# Sheet1.net
KiCad netlist of a schematic drawn in Altium Designer
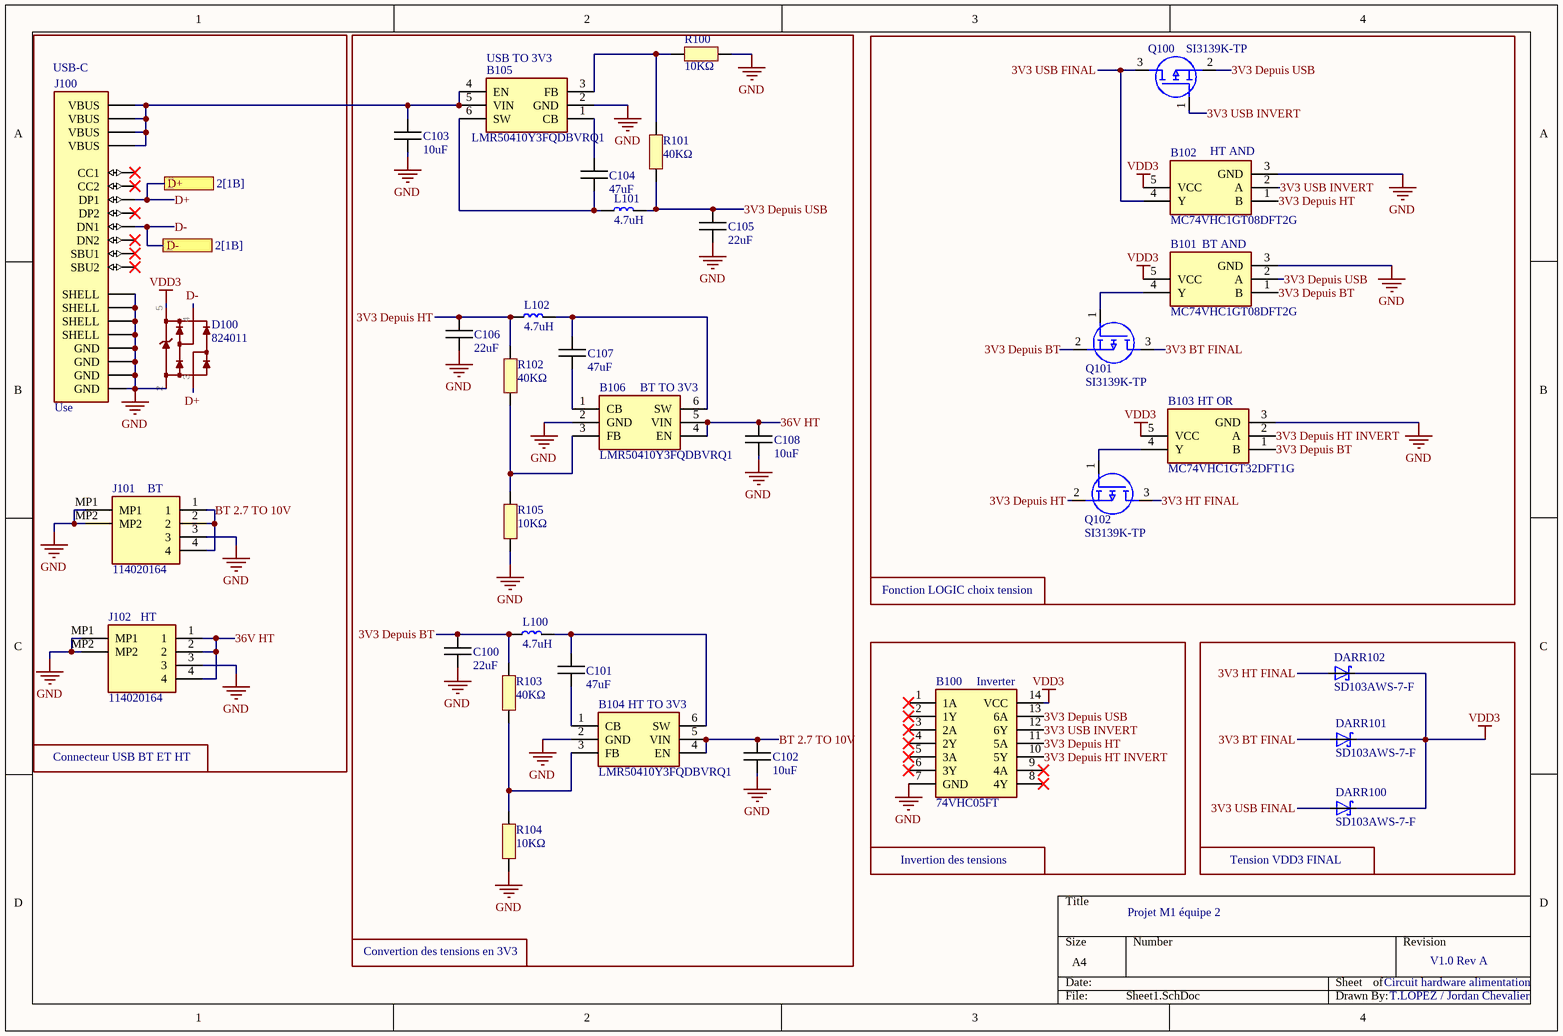
[diagram p0: Sheet1.SchDoc]

(export (version "E")
  (design (tool "Eeschema 10.0.6"))
  (components
    (comp (ref "B100")
      (value "74VHC05FT")
      (footprint "SOP65P640X120-14N")
      (description "Logic Gates CMOS LOGIC IC INVERTER")
      (fields (field (name "MOUSER PART NUMBER") "757-74VHC05FT"))
      (libsource (lib "SCHLibrary") (part "74VHC05FT"))
    )
    (comp (ref "B101")
      (value "MC74VHC1GT08DFT2G")
      (footprint "SOT65P210X110-5N")
      (description "Single 2-Input AND Gate, TTL Level")
      (libsource (lib "SCHLibrary") (part "MC74VHC1GT08DFT2G"))
    )
    (comp (ref "B102")
      (value "MC74VHC1GT08DFT2G")
      (footprint "SOT65P210X110-5N")
      (description "Single 2-Input AND Gate, TTL Level")
      (libsource (lib "SCHLibrary") (part "MC74VHC1GT08DFT2G"))
    )
    (comp (ref "B103")
      (value "MC74VHC1GT32DFT1G")
      (footprint "SOT65P210X110-5N")
      (description "Single 2-Input OR Gate, TTL Level")
      (fields (field (name "MOUSER PART NUMBER") "863-C74VHC1GT32DFT1G"))
      (libsource (lib "SCHLibrary") (part "MC74VHC1GT32DFT1G"))
    )
    (comp (ref "B104")
      (value "LMR50410Y3FQDBVRQ1")
      (footprint "SOT95P280X145-6N")
      (fields (field (name "MOUSER PART NUMBER") "595-R50410Y3FQDBVRQ1"))
      (libsource (lib "SCHLibrary") (part "LMR50410Y3FQDBVRQ1"))
    )
    (comp (ref "B105")
      (value "LMR50410Y3FQDBVRQ1")
      (footprint "SOT95P280X145-6N")
      (fields (field (name "MOUSER PART NUMBER") "595-R50410Y3FQDBVRQ1"))
      (libsource (lib "") (part "LMR50410Y3FQDBVRQ1_1"))
    )
    (comp (ref "B106")
      (value "LMR50410Y3FQDBVRQ1")
      (footprint "SOT95P280X145-6N")
      (fields (field (name "MOUSER PART NUMBER") "595-R50410Y3FQDBVRQ1"))
      (libsource (lib "SCHLibrary") (part "LMR50410Y3FQDBVRQ1"))
    )
    (comp (ref "C100")
      (value "22uF")
      (footprint "CAPC1005X06N")
      (libsource (lib "SCHLibrary") (part "Capacitor"))
    )
    (comp (ref "C101")
      (value "47uF")
      (footprint "CAPC1005X06N")
      (libsource (lib "SCHLibrary") (part "Capacitor"))
    )
    (comp (ref "C102")
      (value "10uF")
      (footprint "CAPC1005X06N")
      (libsource (lib "SCHLibrary") (part "Capacitor"))
    )
    (comp (ref "C103")
      (value "10uF")
      (footprint "CAPC1005X06N")
      (libsource (lib "SCHLibrary") (part "Capacitor"))
    )
    (comp (ref "C104")
      (value "47uF")
      (footprint "CAPC1005X06N")
      (libsource (lib "SCHLibrary") (part "Capacitor"))
    )
    (comp (ref "C105")
      (value "22uF")
      (footprint "CAPC1005X06N")
      (libsource (lib "SCHLibrary") (part "Capacitor"))
    )
    (comp (ref "C106")
      (value "22uF")
      (footprint "CAPC1005X06N")
      (libsource (lib "SCHLibrary") (part "Capacitor"))
    )
    (comp (ref "C107")
      (value "47uF")
      (footprint "CAPC1005X06N")
      (libsource (lib "SCHLibrary") (part "Capacitor"))
    )
    (comp (ref "C108")
      (value "10uF")
      (footprint "CAPC1005X06N")
      (libsource (lib "SCHLibrary") (part "Capacitor"))
    )
    (comp (ref "D100") (value "824011") (footprint "824011") (libsource (lib "SCHLibrary") (part "824011")))
    (comp (ref "DARR100")
      (value "SD103AWS-7-F")
      (footprint "SD103AWS-7-F")
      (description "Diode Array 3 Independent Schottky 40V 175mA Surface Mount 6-TSSOP, SC-88, SOT-363")
      (libsource (lib "SCHLibrary") (part "SD103AWS-7-F"))
    )
    (comp (ref "DARR101")
      (value "SD103AWS-7-F")
      (footprint "SD103AWS-7-F")
      (description "Diode Array 3 Independent Schottky 40V 175mA Surface Mount 6-TSSOP, SC-88, SOT-363")
      (libsource (lib "SCHLibrary") (part "SD103AWS-7-F"))
    )
    (comp (ref "DARR102")
      (value "SD103AWS-7-F")
      (footprint "SD103AWS-7-F")
      (description "Diode Array 3 Independent Schottky 40V 175mA Surface Mount 6-TSSOP, SC-88, SOT-363")
      (libsource (lib "SCHLibrary") (part "SD103AWS-7-F"))
    )
    (comp (ref "J100")
      (value "Use")
      (footprint "USB4085-GF-A")
      (description "Connecteurs USB USB Type C, 2.0, Rec, TH , G/F, RA , Top Mnt, T & R")
      (libsource (lib "SCHLibrary") (part "USB4085-GF-A"))
    )
    (comp (ref "J101")
      (value "114020164")
      (footprint "114020164")
      (description "Seeed Studio Accessories Grove Female Header - SMD-4P-2.0mm-90D-20Pcs")
      (fields (field (name "MOUSER PART NUMBER") "713-114020164"))
      (libsource (lib "SCHLibrary") (part "114020164"))
    )
    (comp (ref "J102")
      (value "114020164")
      (footprint "114020164")
      (description "Seeed Studio Accessories Grove Female Header - SMD-4P-2.0mm-90D-20Pcs")
      (fields (field (name "MOUSER PART NUMBER") "713-114020164"))
      (libsource (lib "SCHLibrary") (part "114020164"))
    )
    (comp (ref "L100")
      (value "4.7uH")
      (footprint "LQPC1005X06N")
      (libsource (lib "SCHLibrary") (part "Bobine"))
    )
    (comp (ref "L101")
      (value "4.7uH")
      (footprint "LQPC1005X06N")
      (libsource (lib "SCHLibrary") (part "Bobine"))
    )
    (comp (ref "L102")
      (value "4.7uH")
      (footprint "LQPC1005X06N")
      (libsource (lib "SCHLibrary") (part "Bobine"))
    )
    (comp (ref "Q100")
      (value "SI3139K-TP")
      (footprint "SI3139K-TP")
      (description "MOSFET P-Channel MOSFET")
      (libsource (lib "SCHLibrary") (part "SI3139K-TP"))
    )
    (comp (ref "Q101")
      (value "SI3139K-TP")
      (footprint "SI3139K-TP")
      (description "MOSFET P-Channel MOSFET")
      (libsource (lib "SCHLibrary") (part "SI3139K-TP"))
    )
    (comp (ref "Q102")
      (value "SI3139K-TP")
      (footprint "SI3139K-TP")
      (description "MOSFET P-Channel MOSFET")
      (libsource (lib "SCHLibrary") (part "SI3139K-TP"))
    )
    (comp (ref "R100") (value "10KΩ") (footprint "RESC1005X06N") (libsource (lib "") (part "Resistor_2")))
    (comp (ref "R101") (value "40KΩ") (footprint "RESC1005X06N") (libsource (lib "") (part "Resistor_1")))
    (comp (ref "R102")
      (value "40KΩ")
      (footprint "RESC1005X06N")
      (libsource (lib "SCHLibrary") (part "Resistor"))
    )
    (comp (ref "R103")
      (value "40KΩ")
      (footprint "RESC1005X06N")
      (libsource (lib "SCHLibrary") (part "Resistor"))
    )
    (comp (ref "R104")
      (value "10KΩ")
      (footprint "RESC1005X06N")
      (libsource (lib "SCHLibrary") (part "Resistor"))
    )
    (comp (ref "R105")
      (value "10KΩ")
      (footprint "RESC1005X06N")
      (libsource (lib "SCHLibrary") (part "Resistor"))
    )
  )
  (nets
    (net (code "1") (name "/3V3 BT FINAL") (class "Default")
      (node (ref "DARR101") (pin "2") (pinfunction "A_2") (pintype "passive"))
      (node (ref "Q101") (pin "3") (pinfunction "D_3") (pintype "passive"))
    )
    (net (code "2") (name "/3V3 Depuis BT") (class "Default")
      (node (ref "B101") (pin "1") (pinfunction "B_1") (pintype "passive"))
      (node (ref "B103") (pin "1") (pinfunction "B_1") (pintype "passive"))
      (node (ref "C100") (pin "1") (pinfunction "1_1") (pintype "passive"))
      (node (ref "L100") (pin "1") (pinfunction "1_1") (pintype "passive"))
      (node (ref "Q101") (pin "2") (pinfunction "S_2") (pintype "passive"))
      (node (ref "R103") (pin "2") (pinfunction "2_2") (pintype "passive"))
    )
    (net (code "3") (name "/3V3 Depuis HT") (class "Default")
      (node (ref "B100") (pin "11") (pinfunction "5A_11") (pintype "passive"))
      (node (ref "B102") (pin "1") (pinfunction "B_1") (pintype "passive"))
      (node (ref "C106") (pin "1") (pinfunction "1_1") (pintype "passive"))
      (node (ref "L102") (pin "1") (pinfunction "1_1") (pintype "passive"))
      (node (ref "Q102") (pin "2") (pinfunction "S_2") (pintype "passive"))
      (node (ref "R102") (pin "2") (pinfunction "2_2") (pintype "passive"))
    )
    (net (code "4") (name "/3V3 Depuis HT INVERT") (class "Default")
      (node (ref "B100") (pin "10") (pinfunction "5Y_10") (pintype "passive"))
      (node (ref "B103") (pin "2") (pinfunction "A_2") (pintype "passive"))
    )
    (net (code "5") (name "/3V3 Depuis USB") (class "Default")
      (node (ref "B100") (pin "13") (pinfunction "6A_13") (pintype "passive"))
      (node (ref "B101") (pin "2") (pinfunction "A_2") (pintype "passive"))
      (node (ref "C105") (pin "1") (pinfunction "1_1") (pintype "passive"))
      (node (ref "L101") (pin "2") (pinfunction "2_2") (pintype "passive"))
      (node (ref "Q100") (pin "2") (pinfunction "S_2") (pintype "passive"))
      (node (ref "R101") (pin "2") (pinfunction "2_2") (pintype "passive"))
    )
    (net (code "6") (name "/3V3 HT FINAL") (class "Default")
      (node (ref "DARR102") (pin "2") (pinfunction "A_2") (pintype "passive"))
      (node (ref "Q102") (pin "3") (pinfunction "D_3") (pintype "passive"))
    )
    (net (code "7") (name "/3V3 USB FINAL") (class "Default")
      (node (ref "B102") (pin "4") (pinfunction "Y_4") (pintype "passive"))
      (node (ref "DARR100") (pin "2") (pinfunction "A_2") (pintype "passive"))
      (node (ref "Q100") (pin "3") (pinfunction "D_3") (pintype "passive"))
    )
    (net (code "8") (name "/3V3 USB INVERT") (class "Default")
      (node (ref "B100") (pin "12") (pinfunction "6Y_12") (pintype "passive"))
      (node (ref "B102") (pin "2") (pinfunction "A_2") (pintype "passive"))
      (node (ref "Q100") (pin "1") (pinfunction "G_1") (pintype "passive"))
    )
    (net (code "9") (name "/36V HT") (class "Default")
      (node (ref "B106") (pin "4") (pinfunction "EN_4") (pintype "passive"))
      (node (ref "B106") (pin "5") (pinfunction "VIN_5") (pintype "passive"))
      (node (ref "C108") (pin "1") (pinfunction "1_1") (pintype "passive"))
      (node (ref "J102") (pin "1") (pinfunction "1_1") (pintype "passive"))
      (node (ref "J102") (pin "2") (pinfunction "2_2") (pintype "passive"))
      (node (ref "J102") (pin "4") (pinfunction "4_4") (pintype "passive"))
    )
    (net (code "10") (name "/BT 2.7 TO 10V") (class "Default")
      (node (ref "B104") (pin "4") (pinfunction "EN_4") (pintype "passive"))
      (node (ref "B104") (pin "5") (pinfunction "VIN_5") (pintype "passive"))
      (node (ref "C102") (pin "1") (pinfunction "1_1") (pintype "passive"))
      (node (ref "J101") (pin "1") (pinfunction "1_1") (pintype "passive"))
      (node (ref "J101") (pin "2") (pinfunction "2_2") (pintype "passive"))
      (node (ref "J101") (pin "4") (pinfunction "4_4") (pintype "passive"))
    )
    (net (code "11") (name "/D+") (class "Default")
      (node (ref "D100") (pin "3") (pinfunction "1_3") (pintype "passive"))
      (node (ref "J100") (pin "A6") (pinfunction "DP1_A6") (pintype "bidirectional"))
    )
    (net (code "12") (name "/D-") (class "Default")
      (node (ref "D100") (pin "4") (pinfunction "2_4") (pintype "passive"))
      (node (ref "J100") (pin "A7") (pinfunction "DN1_A7") (pintype "bidirectional"))
    )
    (net (code "13") (name "GND") (class "Default")
      (node (ref "B100") (pin "7") (pinfunction "GND_7") (pintype "passive"))
      (node (ref "B101") (pin "3") (pinfunction "GND_3") (pintype "passive"))
      (node (ref "B102") (pin "3") (pinfunction "GND_3") (pintype "passive"))
      (node (ref "B103") (pin "3") (pinfunction "GND_3") (pintype "passive"))
      (node (ref "B104") (pin "2") (pinfunction "GND_2") (pintype "passive"))
      (node (ref "B105") (pin "2") (pinfunction "GND_2") (pintype "passive"))
      (node (ref "B106") (pin "2") (pinfunction "GND_2") (pintype "passive"))
      (node (ref "C100") (pin "2") (pinfunction "2_2") (pintype "passive"))
      (node (ref "C102") (pin "2") (pinfunction "2_2") (pintype "passive"))
      (node (ref "C103") (pin "2") (pinfunction "2_2") (pintype "passive"))
      (node (ref "C105") (pin "2") (pinfunction "2_2") (pintype "passive"))
      (node (ref "C106") (pin "2") (pinfunction "2_2") (pintype "passive"))
      (node (ref "C108") (pin "2") (pinfunction "2_2") (pintype "passive"))
      (node (ref "D100") (pin "2") (pinfunction "GND_2") (pintype "power_in"))
      (node (ref "J100") (pin "A1") (pinfunction "GND_A1") (pintype "power_in"))
      (node (ref "J100") (pin "A12") (pinfunction "GND_A12") (pintype "power_in"))
      (node (ref "J100") (pin "B1") (pinfunction "GND_B1") (pintype "power_in"))
      (node (ref "J100") (pin "B12") (pinfunction "GND_B12") (pintype "power_in"))
      (node (ref "J100") (pin "S1") (pinfunction "SHELL_S1") (pintype "passive"))
      (node (ref "J100") (pin "S2") (pinfunction "SHELL_S2") (pintype "passive"))
      (node (ref "J100") (pin "S3") (pinfunction "SHELL_S3") (pintype "passive"))
      (node (ref "J100") (pin "S4") (pinfunction "SHELL_S4") (pintype "passive"))
      (node (ref "J101") (pin "3") (pinfunction "3_3") (pintype "passive"))
      (node (ref "J101") (pin "MP1") (pinfunction "MP1_MP1") (pintype "passive"))
      (node (ref "J101") (pin "MP2") (pinfunction "MP2_MP2") (pintype "passive"))
      (node (ref "J102") (pin "3") (pinfunction "3_3") (pintype "passive"))
      (node (ref "J102") (pin "MP1") (pinfunction "MP1_MP1") (pintype "passive"))
      (node (ref "J102") (pin "MP2") (pinfunction "MP2_MP2") (pintype "passive"))
      (node (ref "R100") (pin "1") (pinfunction "1_1") (pintype "passive"))
      (node (ref "R104") (pin "1") (pinfunction "1_1") (pintype "passive"))
      (node (ref "R105") (pin "1") (pinfunction "1_1") (pintype "passive"))
    )
    (net (code "14") (name "Net-(B101-Y)") (class "Default")
      (node (ref "B101") (pin "4") (pinfunction "Y_4") (pintype "passive"))
      (node (ref "Q101") (pin "1") (pinfunction "G_1") (pintype "passive"))
    )
    (net (code "15") (name "Net-(B103-Y)") (class "Default")
      (node (ref "B103") (pin "4") (pinfunction "Y_4") (pintype "passive"))
      (node (ref "Q102") (pin "1") (pinfunction "G_1") (pintype "passive"))
    )
    (net (code "16") (name "Net-(B104-CB)") (class "Default")
      (node (ref "B104") (pin "1") (pinfunction "CB_1") (pintype "passive"))
      (node (ref "C101") (pin "2") (pinfunction "2_2") (pintype "passive"))
    )
    (net (code "17") (name "Net-(B104-FB)") (class "Default")
      (node (ref "B104") (pin "3") (pinfunction "FB_3") (pintype "passive"))
      (node (ref "R103") (pin "1") (pinfunction "1_1") (pintype "passive"))
      (node (ref "R104") (pin "2") (pinfunction "2_2") (pintype "passive"))
    )
    (net (code "18") (name "Net-(B104-SW)") (class "Default")
      (node (ref "B104") (pin "6") (pinfunction "SW_6") (pintype "passive"))
      (node (ref "C101") (pin "1") (pinfunction "1_1") (pintype "passive"))
      (node (ref "L100") (pin "2") (pinfunction "2_2") (pintype "passive"))
    )
    (net (code "19") (name "Net-(B105-CB)") (class "Default")
      (node (ref "B105") (pin "1") (pinfunction "CB_1") (pintype "passive"))
      (node (ref "C104") (pin "2") (pinfunction "2_2") (pintype "passive"))
    )
    (net (code "20") (name "Net-(B105-EN)") (class "Default")
      (node (ref "B105") (pin "4") (pinfunction "EN_4") (pintype "passive"))
      (node (ref "B105") (pin "5") (pinfunction "VIN_5") (pintype "passive"))
      (node (ref "C103") (pin "1") (pinfunction "1_1") (pintype "passive"))
      (node (ref "J100") (pin "A4") (pinfunction "VBUS_A4") (pintype "power_in"))
      (node (ref "J100") (pin "A9") (pinfunction "VBUS_A9") (pintype "power_in"))
      (node (ref "J100") (pin "B4") (pinfunction "VBUS_B4") (pintype "power_in"))
      (node (ref "J100") (pin "B9") (pinfunction "VBUS_B9") (pintype "power_in"))
    )
    (net (code "21") (name "Net-(B105-FB)") (class "Default")
      (node (ref "B105") (pin "3") (pinfunction "FB_3") (pintype "passive"))
      (node (ref "R100") (pin "2") (pinfunction "2_2") (pintype "passive"))
      (node (ref "R101") (pin "1") (pinfunction "1_1") (pintype "passive"))
    )
    (net (code "22") (name "Net-(B105-SW)") (class "Default")
      (node (ref "B105") (pin "6") (pinfunction "SW_6") (pintype "passive"))
      (node (ref "C104") (pin "1") (pinfunction "1_1") (pintype "passive"))
      (node (ref "L101") (pin "1") (pinfunction "1_1") (pintype "passive"))
    )
    (net (code "23") (name "Net-(B106-CB)") (class "Default")
      (node (ref "B106") (pin "1") (pinfunction "CB_1") (pintype "passive"))
      (node (ref "C107") (pin "2") (pinfunction "2_2") (pintype "passive"))
    )
    (net (code "24") (name "Net-(B106-FB)") (class "Default")
      (node (ref "B106") (pin "3") (pinfunction "FB_3") (pintype "passive"))
      (node (ref "R102") (pin "1") (pinfunction "1_1") (pintype "passive"))
      (node (ref "R105") (pin "2") (pinfunction "2_2") (pintype "passive"))
    )
    (net (code "25") (name "Net-(B106-SW)") (class "Default")
      (node (ref "B106") (pin "6") (pinfunction "SW_6") (pintype "passive"))
      (node (ref "C107") (pin "1") (pinfunction "1_1") (pintype "passive"))
      (node (ref "L102") (pin "2") (pinfunction "2_2") (pintype "passive"))
    )
    (net (code "26") (name "VDD3") (class "Default")
      (node (ref "B100") (pin "14") (pinfunction "VCC_14") (pintype "passive"))
      (node (ref "B101") (pin "5") (pinfunction "VCC_5") (pintype "passive"))
      (node (ref "B102") (pin "5") (pinfunction "VCC_5") (pintype "passive"))
      (node (ref "B103") (pin "5") (pinfunction "VCC_5") (pintype "passive"))
      (node (ref "D100") (pin "5") (pinfunction "VDD_5") (pintype "power_in"))
      (node (ref "DARR100") (pin "1") (pinfunction "C_1") (pintype "passive"))
      (node (ref "DARR101") (pin "1") (pinfunction "C_1") (pintype "passive"))
      (node (ref "DARR102") (pin "1") (pinfunction "C_1") (pintype "passive"))
    )
    (net (code "27") (name "unconnected-(B100-1A-Pad1)") (class "Default")
      (node (ref "B100") (pin "1") (pinfunction "1A_1") (pintype "passive+no_connect"))
    )
    (net (code "28") (name "unconnected-(B100-1Y-Pad2)") (class "Default")
      (node (ref "B100") (pin "2") (pinfunction "1Y_2") (pintype "passive+no_connect"))
    )
    (net (code "29") (name "unconnected-(B100-2A-Pad3)") (class "Default")
      (node (ref "B100") (pin "3") (pinfunction "2A_3") (pintype "passive+no_connect"))
    )
    (net (code "30") (name "unconnected-(B100-2Y-Pad4)") (class "Default")
      (node (ref "B100") (pin "4") (pinfunction "2Y_4") (pintype "passive+no_connect"))
    )
    (net (code "31") (name "unconnected-(B100-3A-Pad5)") (class "Default")
      (node (ref "B100") (pin "5") (pinfunction "3A_5") (pintype "passive+no_connect"))
    )
    (net (code "32") (name "unconnected-(B100-3Y-Pad6)") (class "Default")
      (node (ref "B100") (pin "6") (pinfunction "3Y_6") (pintype "passive+no_connect"))
    )
    (net (code "33") (name "unconnected-(B100-4A-Pad9)") (class "Default")
      (node (ref "B100") (pin "9") (pinfunction "4A_9") (pintype "passive+no_connect"))
    )
    (net (code "34") (name "unconnected-(B100-4Y-Pad8)") (class "Default")
      (node (ref "B100") (pin "8") (pinfunction "4Y_8") (pintype "passive+no_connect"))
    )
    (net (code "35") (name "unconnected-(J100-CC1-PadA5)") (class "Default")
      (node (ref "J100") (pin "A5") (pinfunction "CC1_A5") (pintype "bidirectional+no_connect"))
    )
    (net (code "36") (name "unconnected-(J100-CC2-PadB5)") (class "Default")
      (node (ref "J100") (pin "B5") (pinfunction "CC2_B5") (pintype "bidirectional+no_connect"))
    )
    (net (code "37") (name "unconnected-(J100-DN2-PadB7)") (class "Default")
      (node (ref "J100") (pin "B7") (pinfunction "DN2_B7") (pintype "bidirectional+no_connect"))
    )
    (net (code "38") (name "unconnected-(J100-DP2-PadB6)") (class "Default")
      (node (ref "J100") (pin "B6") (pinfunction "DP2_B6") (pintype "bidirectional+no_connect"))
    )
    (net (code "39") (name "unconnected-(J100-SBU1-PadA8)") (class "Default")
      (node (ref "J100") (pin "A8") (pinfunction "SBU1_A8") (pintype "bidirectional+no_connect"))
    )
    (net (code "40") (name "unconnected-(J100-SBU2-PadB8)") (class "Default")
      (node (ref "J100") (pin "B8") (pinfunction "SBU2_B8") (pintype "bidirectional+no_connect"))
    )
  )
)
